# Pressure_ADIN.net
KiCad netlist of a schematic drawn in Altium Designer
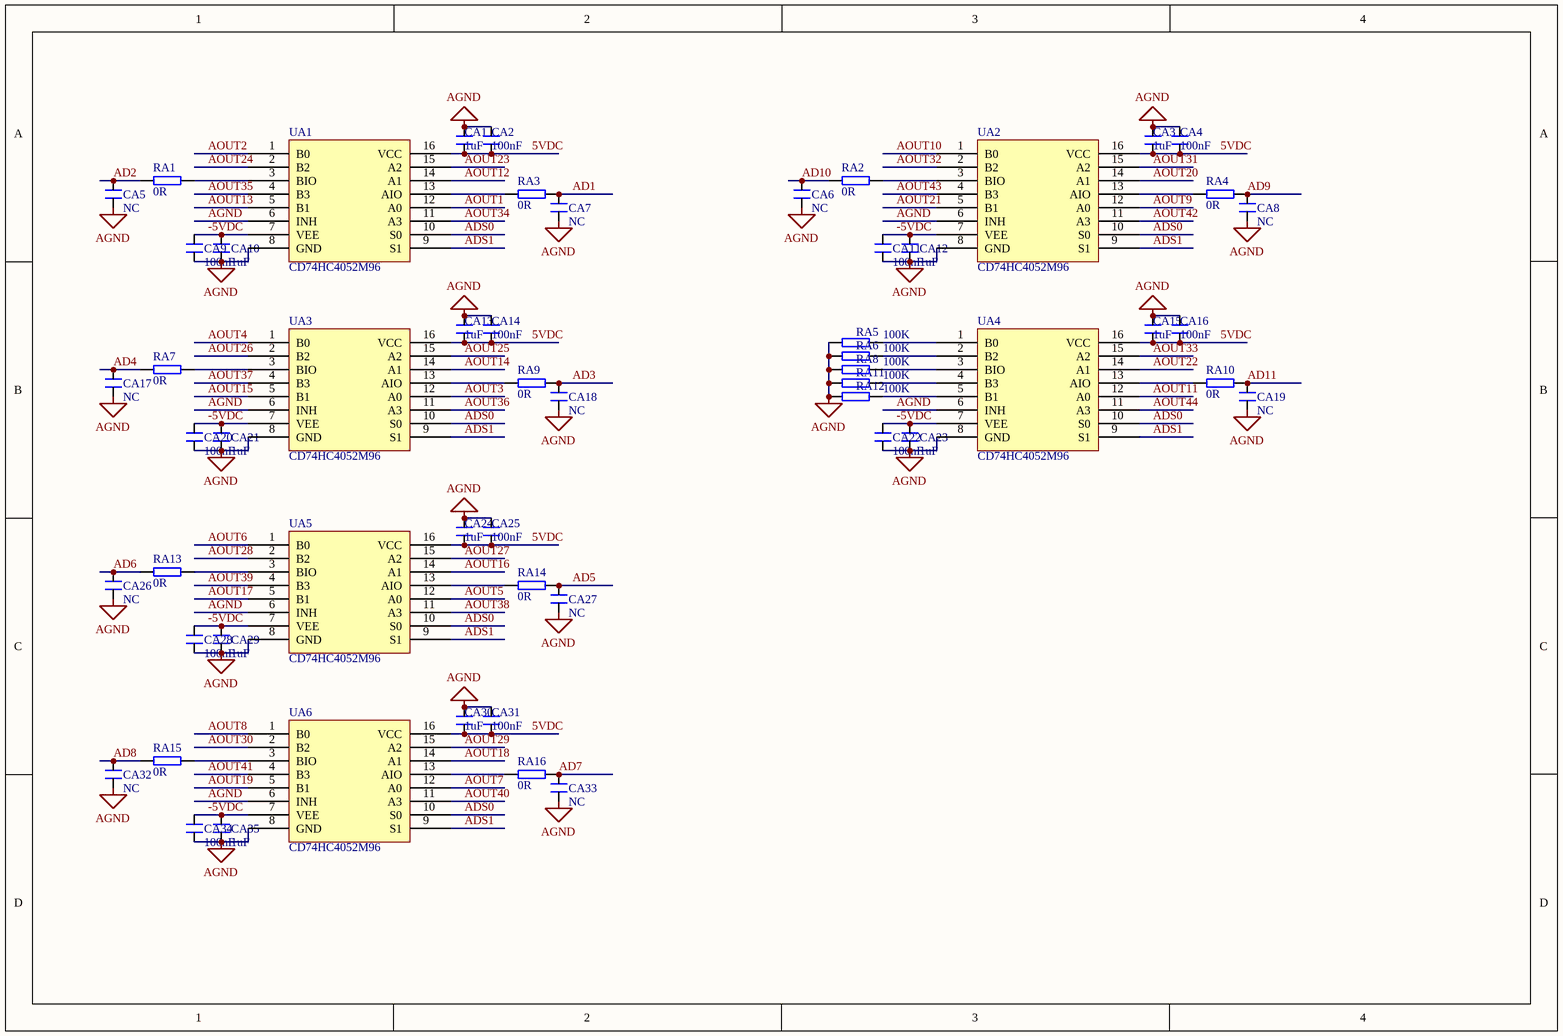
[diagram p0: Pressure_ADIN.SchDoc]

(export (version "E")
  (design (tool "Eeschema 10.0.6"))
  (components
    (comp (ref "CA1") (value "1uF") (footprint "C0603_HSC100") (libsource (lib "*") (part "CAP_M")))
    (comp (ref "CA2") (value "100nF") (footprint "C0603_HSC100") (libsource (lib "*") (part "CAP_M")))
    (comp (ref "CA3") (value "1uF") (footprint "C0603_HSC100") (libsource (lib "*") (part "CAP_M")))
    (comp (ref "CA4") (value "100nF") (footprint "C0603_HSC100") (libsource (lib "*") (part "CAP_M")))
    (comp (ref "CA5") (value "NC") (footprint "C0603_HSC100") (libsource (lib "*") (part "CAP_M")))
    (comp (ref "CA6") (value "NC") (footprint "C0603_HSC100") (libsource (lib "*") (part "CAP_M")))
    (comp (ref "CA7") (value "NC") (footprint "C0603_HSC100") (libsource (lib "*") (part "CAP_M")))
    (comp (ref "CA8") (value "NC") (footprint "C0603_HSC100") (libsource (lib "*") (part "CAP_M")))
    (comp (ref "CA9") (value "100nF") (footprint "C0603_HSC100") (libsource (lib "*") (part "CAP_M")))
    (comp (ref "CA10") (value "1uF") (footprint "C0603_HSC100") (libsource (lib "*") (part "CAP_M")))
    (comp (ref "CA11") (value "100nF") (footprint "C0603_HSC100") (libsource (lib "*") (part "CAP_M")))
    (comp (ref "CA12") (value "1uF") (footprint "C0603_HSC100") (libsource (lib "*") (part "CAP_M")))
    (comp (ref "CA13") (value "1uF") (footprint "C0603_HSC100") (libsource (lib "*") (part "CAP_M")))
    (comp (ref "CA14") (value "100nF") (footprint "C0603_HSC100") (libsource (lib "*") (part "CAP_M")))
    (comp (ref "CA15") (value "1uF") (footprint "C0603_HSC100") (libsource (lib "*") (part "CAP_M")))
    (comp (ref "CA16") (value "100nF") (footprint "C0603_HSC100") (libsource (lib "*") (part "CAP_M")))
    (comp (ref "CA17") (value "NC") (footprint "C0603_HSC100") (libsource (lib "*") (part "CAP_M")))
    (comp (ref "CA18") (value "NC") (footprint "C0603_HSC100") (libsource (lib "*") (part "CAP_M")))
    (comp (ref "CA19") (value "NC") (footprint "C0603_HSC100") (libsource (lib "*") (part "CAP_M")))
    (comp (ref "CA20") (value "100nF") (footprint "C0603_HSC100") (libsource (lib "*") (part "CAP_M")))
    (comp (ref "CA21") (value "1uF") (footprint "C0603_HSC100") (libsource (lib "*") (part "CAP_M")))
    (comp (ref "CA22") (value "100nF") (footprint "C0603_HSC100") (libsource (lib "*") (part "CAP_M")))
    (comp (ref "CA23") (value "1uF") (footprint "C0603_HSC100") (libsource (lib "*") (part "CAP_M")))
    (comp (ref "CA24") (value "1uF") (footprint "C0603_HSC100") (libsource (lib "*") (part "CAP_M")))
    (comp (ref "CA25") (value "100nF") (footprint "C0603_HSC100") (libsource (lib "*") (part "CAP_M")))
    (comp (ref "CA26") (value "NC") (footprint "C0603_HSC100") (libsource (lib "*") (part "CAP_M")))
    (comp (ref "CA27") (value "NC") (footprint "C0603_HSC100") (libsource (lib "*") (part "CAP_M")))
    (comp (ref "CA28") (value "100nF") (footprint "C0603_HSC100") (libsource (lib "*") (part "CAP_M")))
    (comp (ref "CA29") (value "1uF") (footprint "C0603_HSC100") (libsource (lib "*") (part "CAP_M")))
    (comp (ref "CA30") (value "1uF") (footprint "C0603_HSC100") (libsource (lib "*") (part "CAP_M")))
    (comp (ref "CA31") (value "100nF") (footprint "C0603_HSC100") (libsource (lib "*") (part "CAP_M")))
    (comp (ref "CA32") (value "NC") (footprint "C0603_HSC100") (libsource (lib "*") (part "CAP_M")))
    (comp (ref "CA33") (value "NC") (footprint "C0603_HSC100") (libsource (lib "*") (part "CAP_M")))
    (comp (ref "CA34") (value "100nF") (footprint "C0603_HSC100") (libsource (lib "*") (part "CAP_M")))
    (comp (ref "CA35") (value "1uF") (footprint "C0603_HSC100") (libsource (lib "*") (part "CAP_M")))
    (comp (ref "RA1") (value "0R") (footprint "R0603_HSC100") (libsource (lib "*") (part "RES")))
    (comp (ref "RA2") (value "0R") (footprint "R0603_HSC100") (libsource (lib "*") (part "RES")))
    (comp (ref "RA3") (value "0R") (footprint "R0603_HSC100") (libsource (lib "*") (part "RES")))
    (comp (ref "RA4") (value "0R") (footprint "R0603_HSC100") (libsource (lib "*") (part "RES")))
    (comp (ref "RA5") (value "100K") (footprint "R0603_HSC100") (libsource (lib "*") (part "RES")))
    (comp (ref "RA6") (value "100K") (footprint "R0603_HSC100") (libsource (lib "*") (part "RES")))
    (comp (ref "RA7") (value "0R") (footprint "R0603_HSC100") (libsource (lib "*") (part "RES")))
    (comp (ref "RA8") (value "100K") (footprint "R0603_HSC100") (libsource (lib "*") (part "RES")))
    (comp (ref "RA9") (value "0R") (footprint "R0603_HSC100") (libsource (lib "*") (part "RES")))
    (comp (ref "RA10") (value "0R") (footprint "R0603_HSC100") (libsource (lib "*") (part "RES")))
    (comp (ref "RA11") (value "100K") (footprint "R0603_HSC100") (libsource (lib "*") (part "RES")))
    (comp (ref "RA12") (value "100K") (footprint "R0603_HSC100") (libsource (lib "*") (part "RES")))
    (comp (ref "RA13") (value "0R") (footprint "R0603_HSC100") (libsource (lib "*") (part "RES")))
    (comp (ref "RA14") (value "0R") (footprint "R0603_HSC100") (libsource (lib "*") (part "RES")))
    (comp (ref "RA15") (value "0R") (footprint "R0603_HSC100") (libsource (lib "*") (part "RES")))
    (comp (ref "RA16") (value "0R") (footprint "R0603_HSC100") (libsource (lib "*") (part "RES")))
    (comp (ref "UA1")
      (value "CD74HC4052M96")
      (footprint "SO-16")
      (description "74HC4052")
      (libsource (lib "MY_SCH") (part "74HC4052"))
    )
    (comp (ref "UA2")
      (value "CD74HC4052M96")
      (footprint "SO-16")
      (description "74HC4052")
      (libsource (lib "MY_SCH") (part "74HC4052"))
    )
    (comp (ref "UA3")
      (value "CD74HC4052M96")
      (footprint "SO-16")
      (description "74HC4052")
      (libsource (lib "MY_SCH") (part "74HC4052"))
    )
    (comp (ref "UA4")
      (value "CD74HC4052M96")
      (footprint "SO-16")
      (description "74HC4052")
      (libsource (lib "MY_SCH") (part "74HC4052"))
    )
    (comp (ref "UA5")
      (value "CD74HC4052M96")
      (footprint "SO-16")
      (description "74HC4052")
      (libsource (lib "MY_SCH") (part "74HC4052"))
    )
    (comp (ref "UA6")
      (value "CD74HC4052M96")
      (footprint "SO-16")
      (description "74HC4052")
      (libsource (lib "MY_SCH") (part "74HC4052"))
    )
  )
  (nets
    (net (code "1") (name "/-5VDC") (class "Default")
      (node (ref "CA10") (pin "2") (pintype "passive"))
      (node (ref "CA11") (pin "2") (pintype "passive"))
      (node (ref "CA12") (pin "2") (pintype "passive"))
      (node (ref "CA20") (pin "2") (pintype "passive"))
      (node (ref "CA21") (pin "2") (pintype "passive"))
      (node (ref "CA22") (pin "2") (pintype "passive"))
      (node (ref "CA23") (pin "2") (pintype "passive"))
      (node (ref "CA28") (pin "2") (pintype "passive"))
      (node (ref "CA29") (pin "2") (pintype "passive"))
      (node (ref "CA34") (pin "2") (pintype "passive"))
      (node (ref "CA35") (pin "2") (pintype "passive"))
      (node (ref "CA9") (pin "2") (pintype "passive"))
      (node (ref "UA1") (pin "7") (pinfunction "VEE_7") (pintype "passive"))
      (node (ref "UA2") (pin "7") (pinfunction "VEE_7") (pintype "passive"))
      (node (ref "UA3") (pin "7") (pinfunction "VEE_7") (pintype "passive"))
      (node (ref "UA4") (pin "7") (pinfunction "VEE_7") (pintype "passive"))
      (node (ref "UA5") (pin "7") (pinfunction "VEE_7") (pintype "passive"))
      (node (ref "UA6") (pin "7") (pinfunction "VEE_7") (pintype "passive"))
    )
    (net (code "2") (name "/5VDC") (class "Default")
      (node (ref "CA1") (pin "2") (pintype "passive"))
      (node (ref "CA13") (pin "2") (pintype "passive"))
      (node (ref "CA14") (pin "2") (pintype "passive"))
      (node (ref "CA15") (pin "2") (pintype "passive"))
      (node (ref "CA16") (pin "2") (pintype "passive"))
      (node (ref "CA2") (pin "2") (pintype "passive"))
      (node (ref "CA24") (pin "2") (pintype "passive"))
      (node (ref "CA25") (pin "2") (pintype "passive"))
      (node (ref "CA3") (pin "2") (pintype "passive"))
      (node (ref "CA30") (pin "2") (pintype "passive"))
      (node (ref "CA31") (pin "2") (pintype "passive"))
      (node (ref "CA4") (pin "2") (pintype "passive"))
      (node (ref "UA1") (pin "16") (pinfunction "VCC_16") (pintype "tri_state"))
      (node (ref "UA2") (pin "16") (pinfunction "VCC_16") (pintype "tri_state"))
      (node (ref "UA3") (pin "16") (pinfunction "VCC_16") (pintype "tri_state"))
      (node (ref "UA4") (pin "16") (pinfunction "VCC_16") (pintype "tri_state"))
      (node (ref "UA5") (pin "16") (pinfunction "VCC_16") (pintype "tri_state"))
      (node (ref "UA6") (pin "16") (pinfunction "VCC_16") (pintype "tri_state"))
    )
    (net (code "3") (name "/AD1") (class "Default")
      (node (ref "CA7") (pin "2") (pintype "passive"))
      (node (ref "RA3") (pin "1") (pintype "passive"))
    )
    (net (code "4") (name "/AD2") (class "Default")
      (node (ref "CA5") (pin "2") (pintype "passive"))
      (node (ref "RA1") (pin "2") (pintype "passive"))
    )
    (net (code "5") (name "/AD3") (class "Default")
      (node (ref "CA18") (pin "2") (pintype "passive"))
      (node (ref "RA9") (pin "1") (pintype "passive"))
    )
    (net (code "6") (name "/AD4") (class "Default")
      (node (ref "CA17") (pin "2") (pintype "passive"))
      (node (ref "RA7") (pin "2") (pintype "passive"))
    )
    (net (code "7") (name "/AD5") (class "Default")
      (node (ref "CA27") (pin "2") (pintype "passive"))
      (node (ref "RA14") (pin "1") (pintype "passive"))
    )
    (net (code "8") (name "/AD6") (class "Default")
      (node (ref "CA26") (pin "2") (pintype "passive"))
      (node (ref "RA13") (pin "2") (pintype "passive"))
    )
    (net (code "9") (name "/AD7") (class "Default")
      (node (ref "CA33") (pin "2") (pintype "passive"))
      (node (ref "RA16") (pin "1") (pintype "passive"))
    )
    (net (code "10") (name "/AD8") (class "Default")
      (node (ref "CA32") (pin "2") (pintype "passive"))
      (node (ref "RA15") (pin "2") (pintype "passive"))
    )
    (net (code "11") (name "/AD9") (class "Default")
      (node (ref "CA8") (pin "2") (pintype "passive"))
      (node (ref "RA4") (pin "1") (pintype "passive"))
    )
    (net (code "12") (name "/AD10") (class "Default")
      (node (ref "CA6") (pin "2") (pintype "passive"))
      (node (ref "RA2") (pin "2") (pintype "passive"))
    )
    (net (code "13") (name "/AD11") (class "Default")
      (node (ref "CA19") (pin "2") (pintype "passive"))
      (node (ref "RA10") (pin "1") (pintype "passive"))
    )
    (net (code "14") (name "/ADS0") (class "Default")
      (node (ref "UA1") (pin "10") (pinfunction "S0_10") (pintype "tri_state"))
      (node (ref "UA2") (pin "10") (pinfunction "S0_10") (pintype "tri_state"))
      (node (ref "UA3") (pin "10") (pinfunction "S0_10") (pintype "tri_state"))
      (node (ref "UA4") (pin "10") (pinfunction "S0_10") (pintype "tri_state"))
      (node (ref "UA5") (pin "10") (pinfunction "S0_10") (pintype "tri_state"))
      (node (ref "UA6") (pin "10") (pinfunction "S0_10") (pintype "tri_state"))
    )
    (net (code "15") (name "/ADS1") (class "Default")
      (node (ref "UA1") (pin "9") (pinfunction "S1_9") (pintype "tri_state"))
      (node (ref "UA2") (pin "9") (pinfunction "S1_9") (pintype "tri_state"))
      (node (ref "UA3") (pin "9") (pinfunction "S1_9") (pintype "tri_state"))
      (node (ref "UA4") (pin "9") (pinfunction "S1_9") (pintype "tri_state"))
      (node (ref "UA5") (pin "9") (pinfunction "S1_9") (pintype "tri_state"))
      (node (ref "UA6") (pin "9") (pinfunction "S1_9") (pintype "tri_state"))
    )
    (net (code "16") (name "/AOUT1") (class "Default")
      (node (ref "UA1") (pin "12") (pinfunction "A0_12") (pintype "tri_state"))
    )
    (net (code "17") (name "/AOUT2") (class "Default")
      (node (ref "UA1") (pin "1") (pinfunction "B0_1") (pintype "passive"))
    )
    (net (code "18") (name "/AOUT3") (class "Default")
      (node (ref "UA3") (pin "12") (pinfunction "A0_12") (pintype "tri_state"))
    )
    (net (code "19") (name "/AOUT4") (class "Default")
      (node (ref "UA3") (pin "1") (pinfunction "B0_1") (pintype "passive"))
    )
    (net (code "20") (name "/AOUT5") (class "Default")
      (node (ref "UA5") (pin "12") (pinfunction "A0_12") (pintype "tri_state"))
    )
    (net (code "21") (name "/AOUT6") (class "Default")
      (node (ref "UA5") (pin "1") (pinfunction "B0_1") (pintype "passive"))
    )
    (net (code "22") (name "/AOUT7") (class "Default")
      (node (ref "UA6") (pin "12") (pinfunction "A0_12") (pintype "tri_state"))
    )
    (net (code "23") (name "/AOUT8") (class "Default")
      (node (ref "UA6") (pin "1") (pinfunction "B0_1") (pintype "passive"))
    )
    (net (code "24") (name "/AOUT9") (class "Default")
      (node (ref "UA2") (pin "12") (pinfunction "A0_12") (pintype "tri_state"))
    )
    (net (code "25") (name "/AOUT10") (class "Default")
      (node (ref "UA2") (pin "1") (pinfunction "B0_1") (pintype "passive"))
    )
    (net (code "26") (name "/AOUT11") (class "Default")
      (node (ref "UA4") (pin "12") (pinfunction "A0_12") (pintype "tri_state"))
    )
    (net (code "27") (name "/AOUT12") (class "Default")
      (node (ref "UA1") (pin "14") (pinfunction "A1_14") (pintype "tri_state"))
    )
    (net (code "28") (name "/AOUT13") (class "Default")
      (node (ref "UA1") (pin "5") (pinfunction "B1_5") (pintype "passive"))
    )
    (net (code "29") (name "/AOUT14") (class "Default")
      (node (ref "UA3") (pin "14") (pinfunction "A1_14") (pintype "tri_state"))
    )
    (net (code "30") (name "/AOUT15") (class "Default")
      (node (ref "UA3") (pin "5") (pinfunction "B1_5") (pintype "passive"))
    )
    (net (code "31") (name "/AOUT16") (class "Default")
      (node (ref "UA5") (pin "14") (pinfunction "A1_14") (pintype "tri_state"))
    )
    (net (code "32") (name "/AOUT17") (class "Default")
      (node (ref "UA5") (pin "5") (pinfunction "B1_5") (pintype "passive"))
    )
    (net (code "33") (name "/AOUT18") (class "Default")
      (node (ref "UA6") (pin "14") (pinfunction "A1_14") (pintype "tri_state"))
    )
    (net (code "34") (name "/AOUT19") (class "Default")
      (node (ref "UA6") (pin "5") (pinfunction "B1_5") (pintype "passive"))
    )
    (net (code "35") (name "/AOUT20") (class "Default")
      (node (ref "UA2") (pin "14") (pinfunction "A1_14") (pintype "tri_state"))
    )
    (net (code "36") (name "/AOUT21") (class "Default")
      (node (ref "UA2") (pin "5") (pinfunction "B1_5") (pintype "passive"))
    )
    (net (code "37") (name "/AOUT22") (class "Default")
      (node (ref "UA4") (pin "14") (pinfunction "A1_14") (pintype "tri_state"))
    )
    (net (code "38") (name "/AOUT23") (class "Default")
      (node (ref "UA1") (pin "15") (pinfunction "A2_15") (pintype "tri_state"))
    )
    (net (code "39") (name "/AOUT24") (class "Default")
      (node (ref "UA1") (pin "2") (pinfunction "B2_2") (pintype "passive"))
    )
    (net (code "40") (name "/AOUT25") (class "Default")
      (node (ref "UA3") (pin "15") (pinfunction "A2_15") (pintype "tri_state"))
    )
    (net (code "41") (name "/AOUT26") (class "Default")
      (node (ref "UA3") (pin "2") (pinfunction "B2_2") (pintype "passive"))
    )
    (net (code "42") (name "/AOUT27") (class "Default")
      (node (ref "UA5") (pin "15") (pinfunction "A2_15") (pintype "tri_state"))
    )
    (net (code "43") (name "/AOUT28") (class "Default")
      (node (ref "UA5") (pin "2") (pinfunction "B2_2") (pintype "passive"))
    )
    (net (code "44") (name "/AOUT29") (class "Default")
      (node (ref "UA6") (pin "15") (pinfunction "A2_15") (pintype "tri_state"))
    )
    (net (code "45") (name "/AOUT30") (class "Default")
      (node (ref "UA6") (pin "2") (pinfunction "B2_2") (pintype "passive"))
    )
    (net (code "46") (name "/AOUT31") (class "Default")
      (node (ref "UA2") (pin "15") (pinfunction "A2_15") (pintype "tri_state"))
    )
    (net (code "47") (name "/AOUT32") (class "Default")
      (node (ref "UA2") (pin "2") (pinfunction "B2_2") (pintype "passive"))
    )
    (net (code "48") (name "/AOUT33") (class "Default")
      (node (ref "UA4") (pin "15") (pinfunction "A2_15") (pintype "tri_state"))
    )
    (net (code "49") (name "/AOUT34") (class "Default")
      (node (ref "UA1") (pin "11") (pinfunction "A3_11") (pintype "tri_state"))
    )
    (net (code "50") (name "/AOUT35") (class "Default")
      (node (ref "UA1") (pin "4") (pinfunction "B3_4") (pintype "passive"))
    )
    (net (code "51") (name "/AOUT36") (class "Default")
      (node (ref "UA3") (pin "11") (pinfunction "A3_11") (pintype "tri_state"))
    )
    (net (code "52") (name "/AOUT37") (class "Default")
      (node (ref "UA3") (pin "4") (pinfunction "B3_4") (pintype "passive"))
    )
    (net (code "53") (name "/AOUT38") (class "Default")
      (node (ref "UA5") (pin "11") (pinfunction "A3_11") (pintype "tri_state"))
    )
    (net (code "54") (name "/AOUT39") (class "Default")
      (node (ref "UA5") (pin "4") (pinfunction "B3_4") (pintype "passive"))
    )
    (net (code "55") (name "/AOUT40") (class "Default")
      (node (ref "UA6") (pin "11") (pinfunction "A3_11") (pintype "tri_state"))
    )
    (net (code "56") (name "/AOUT41") (class "Default")
      (node (ref "UA6") (pin "4") (pinfunction "B3_4") (pintype "passive"))
    )
    (net (code "57") (name "/AOUT42") (class "Default")
      (node (ref "UA2") (pin "11") (pinfunction "A3_11") (pintype "tri_state"))
    )
    (net (code "58") (name "/AOUT43") (class "Default")
      (node (ref "UA2") (pin "4") (pinfunction "B3_4") (pintype "passive"))
    )
    (net (code "59") (name "/AOUT44") (class "Default")
      (node (ref "UA4") (pin "11") (pinfunction "A3_11") (pintype "tri_state"))
    )
    (net (code "60") (name "AGND") (class "Default")
      (node (ref "CA1") (pin "1") (pintype "passive"))
      (node (ref "CA10") (pin "1") (pintype "passive"))
      (node (ref "CA11") (pin "1") (pintype "passive"))
      (node (ref "CA12") (pin "1") (pintype "passive"))
      (node (ref "CA13") (pin "1") (pintype "passive"))
      (node (ref "CA14") (pin "1") (pintype "passive"))
      (node (ref "CA15") (pin "1") (pintype "passive"))
      (node (ref "CA16") (pin "1") (pintype "passive"))
      (node (ref "CA17") (pin "1") (pintype "passive"))
      (node (ref "CA18") (pin "1") (pintype "passive"))
      (node (ref "CA19") (pin "1") (pintype "passive"))
      (node (ref "CA2") (pin "1") (pintype "passive"))
      (node (ref "CA20") (pin "1") (pintype "passive"))
      (node (ref "CA21") (pin "1") (pintype "passive"))
      (node (ref "CA22") (pin "1") (pintype "passive"))
      (node (ref "CA23") (pin "1") (pintype "passive"))
      (node (ref "CA24") (pin "1") (pintype "passive"))
      (node (ref "CA25") (pin "1") (pintype "passive"))
      (node (ref "CA26") (pin "1") (pintype "passive"))
      (node (ref "CA27") (pin "1") (pintype "passive"))
      (node (ref "CA28") (pin "1") (pintype "passive"))
      (node (ref "CA29") (pin "1") (pintype "passive"))
      (node (ref "CA3") (pin "1") (pintype "passive"))
      (node (ref "CA30") (pin "1") (pintype "passive"))
      (node (ref "CA31") (pin "1") (pintype "passive"))
      (node (ref "CA32") (pin "1") (pintype "passive"))
      (node (ref "CA33") (pin "1") (pintype "passive"))
      (node (ref "CA34") (pin "1") (pintype "passive"))
      (node (ref "CA35") (pin "1") (pintype "passive"))
      (node (ref "CA4") (pin "1") (pintype "passive"))
      (node (ref "CA5") (pin "1") (pintype "passive"))
      (node (ref "CA6") (pin "1") (pintype "passive"))
      (node (ref "CA7") (pin "1") (pintype "passive"))
      (node (ref "CA8") (pin "1") (pintype "passive"))
      (node (ref "CA9") (pin "1") (pintype "passive"))
      (node (ref "RA11") (pin "1") (pintype "passive"))
      (node (ref "RA12") (pin "1") (pintype "passive"))
      (node (ref "RA5") (pin "1") (pintype "passive"))
      (node (ref "RA6") (pin "1") (pintype "passive"))
      (node (ref "RA8") (pin "1") (pintype "passive"))
      (node (ref "UA1") (pin "6") (pinfunction "INH_6") (pintype "passive"))
      (node (ref "UA1") (pin "8") (pinfunction "GND_8") (pintype "tri_state"))
      (node (ref "UA2") (pin "6") (pinfunction "INH_6") (pintype "passive"))
      (node (ref "UA2") (pin "8") (pinfunction "GND_8") (pintype "tri_state"))
      (node (ref "UA3") (pin "6") (pinfunction "INH_6") (pintype "passive"))
      (node (ref "UA3") (pin "8") (pinfunction "GND_8") (pintype "tri_state"))
      (node (ref "UA4") (pin "6") (pinfunction "INH_6") (pintype "passive"))
      (node (ref "UA4") (pin "8") (pinfunction "GND_8") (pintype "tri_state"))
      (node (ref "UA5") (pin "6") (pinfunction "INH_6") (pintype "passive"))
      (node (ref "UA5") (pin "8") (pinfunction "GND_8") (pintype "tri_state"))
      (node (ref "UA6") (pin "6") (pinfunction "INH_6") (pintype "passive"))
      (node (ref "UA6") (pin "8") (pinfunction "GND_8") (pintype "tri_state"))
    )
    (net (code "61") (name "Net-(UA1-AIO)") (class "Default")
      (node (ref "RA3") (pin "2") (pintype "passive"))
      (node (ref "UA1") (pin "13") (pinfunction "AIO_13") (pintype "tri_state"))
    )
    (net (code "62") (name "Net-(UA1-BIO)") (class "Default")
      (node (ref "RA1") (pin "1") (pintype "passive"))
      (node (ref "UA1") (pin "3") (pinfunction "BIO_3") (pintype "passive"))
    )
    (net (code "63") (name "Net-(UA2-AIO)") (class "Default")
      (node (ref "RA4") (pin "2") (pintype "passive"))
      (node (ref "UA2") (pin "13") (pinfunction "AIO_13") (pintype "tri_state"))
    )
    (net (code "64") (name "Net-(UA2-BIO)") (class "Default")
      (node (ref "RA2") (pin "1") (pintype "passive"))
      (node (ref "UA2") (pin "3") (pinfunction "BIO_3") (pintype "passive"))
    )
    (net (code "65") (name "Net-(UA3-AIO)") (class "Default")
      (node (ref "RA9") (pin "2") (pintype "passive"))
      (node (ref "UA3") (pin "13") (pinfunction "AIO_13") (pintype "tri_state"))
    )
    (net (code "66") (name "Net-(UA3-BIO)") (class "Default")
      (node (ref "RA7") (pin "1") (pintype "passive"))
      (node (ref "UA3") (pin "3") (pinfunction "BIO_3") (pintype "passive"))
    )
    (net (code "67") (name "Net-(UA4-AIO)") (class "Default")
      (node (ref "RA10") (pin "2") (pintype "passive"))
      (node (ref "UA4") (pin "13") (pinfunction "AIO_13") (pintype "tri_state"))
    )
    (net (code "68") (name "Net-(UA4-B0)") (class "Default")
      (node (ref "RA5") (pin "2") (pintype "passive"))
      (node (ref "UA4") (pin "1") (pinfunction "B0_1") (pintype "passive"))
    )
    (net (code "69") (name "Net-(UA4-B1)") (class "Default")
      (node (ref "RA12") (pin "2") (pintype "passive"))
      (node (ref "UA4") (pin "5") (pinfunction "B1_5") (pintype "passive"))
    )
    (net (code "70") (name "Net-(UA4-B2)") (class "Default")
      (node (ref "RA6") (pin "2") (pintype "passive"))
      (node (ref "UA4") (pin "2") (pinfunction "B2_2") (pintype "passive"))
    )
    (net (code "71") (name "Net-(UA4-B3)") (class "Default")
      (node (ref "RA11") (pin "2") (pintype "passive"))
      (node (ref "UA4") (pin "4") (pinfunction "B3_4") (pintype "passive"))
    )
    (net (code "72") (name "Net-(UA4-BIO)") (class "Default")
      (node (ref "RA8") (pin "2") (pintype "passive"))
      (node (ref "UA4") (pin "3") (pinfunction "BIO_3") (pintype "passive"))
    )
    (net (code "73") (name "Net-(UA5-AIO)") (class "Default")
      (node (ref "RA14") (pin "2") (pintype "passive"))
      (node (ref "UA5") (pin "13") (pinfunction "AIO_13") (pintype "tri_state"))
    )
    (net (code "74") (name "Net-(UA5-BIO)") (class "Default")
      (node (ref "RA13") (pin "1") (pintype "passive"))
      (node (ref "UA5") (pin "3") (pinfunction "BIO_3") (pintype "passive"))
    )
    (net (code "75") (name "Net-(UA6-AIO)") (class "Default")
      (node (ref "RA16") (pin "2") (pintype "passive"))
      (node (ref "UA6") (pin "13") (pinfunction "AIO_13") (pintype "tri_state"))
    )
    (net (code "76") (name "Net-(UA6-BIO)") (class "Default")
      (node (ref "RA15") (pin "1") (pintype "passive"))
      (node (ref "UA6") (pin "3") (pinfunction "BIO_3") (pintype "passive"))
    )
  )
)
